# mikrobus-relay-1.net
KiCad netlist of a schematic drawn in EAGLE
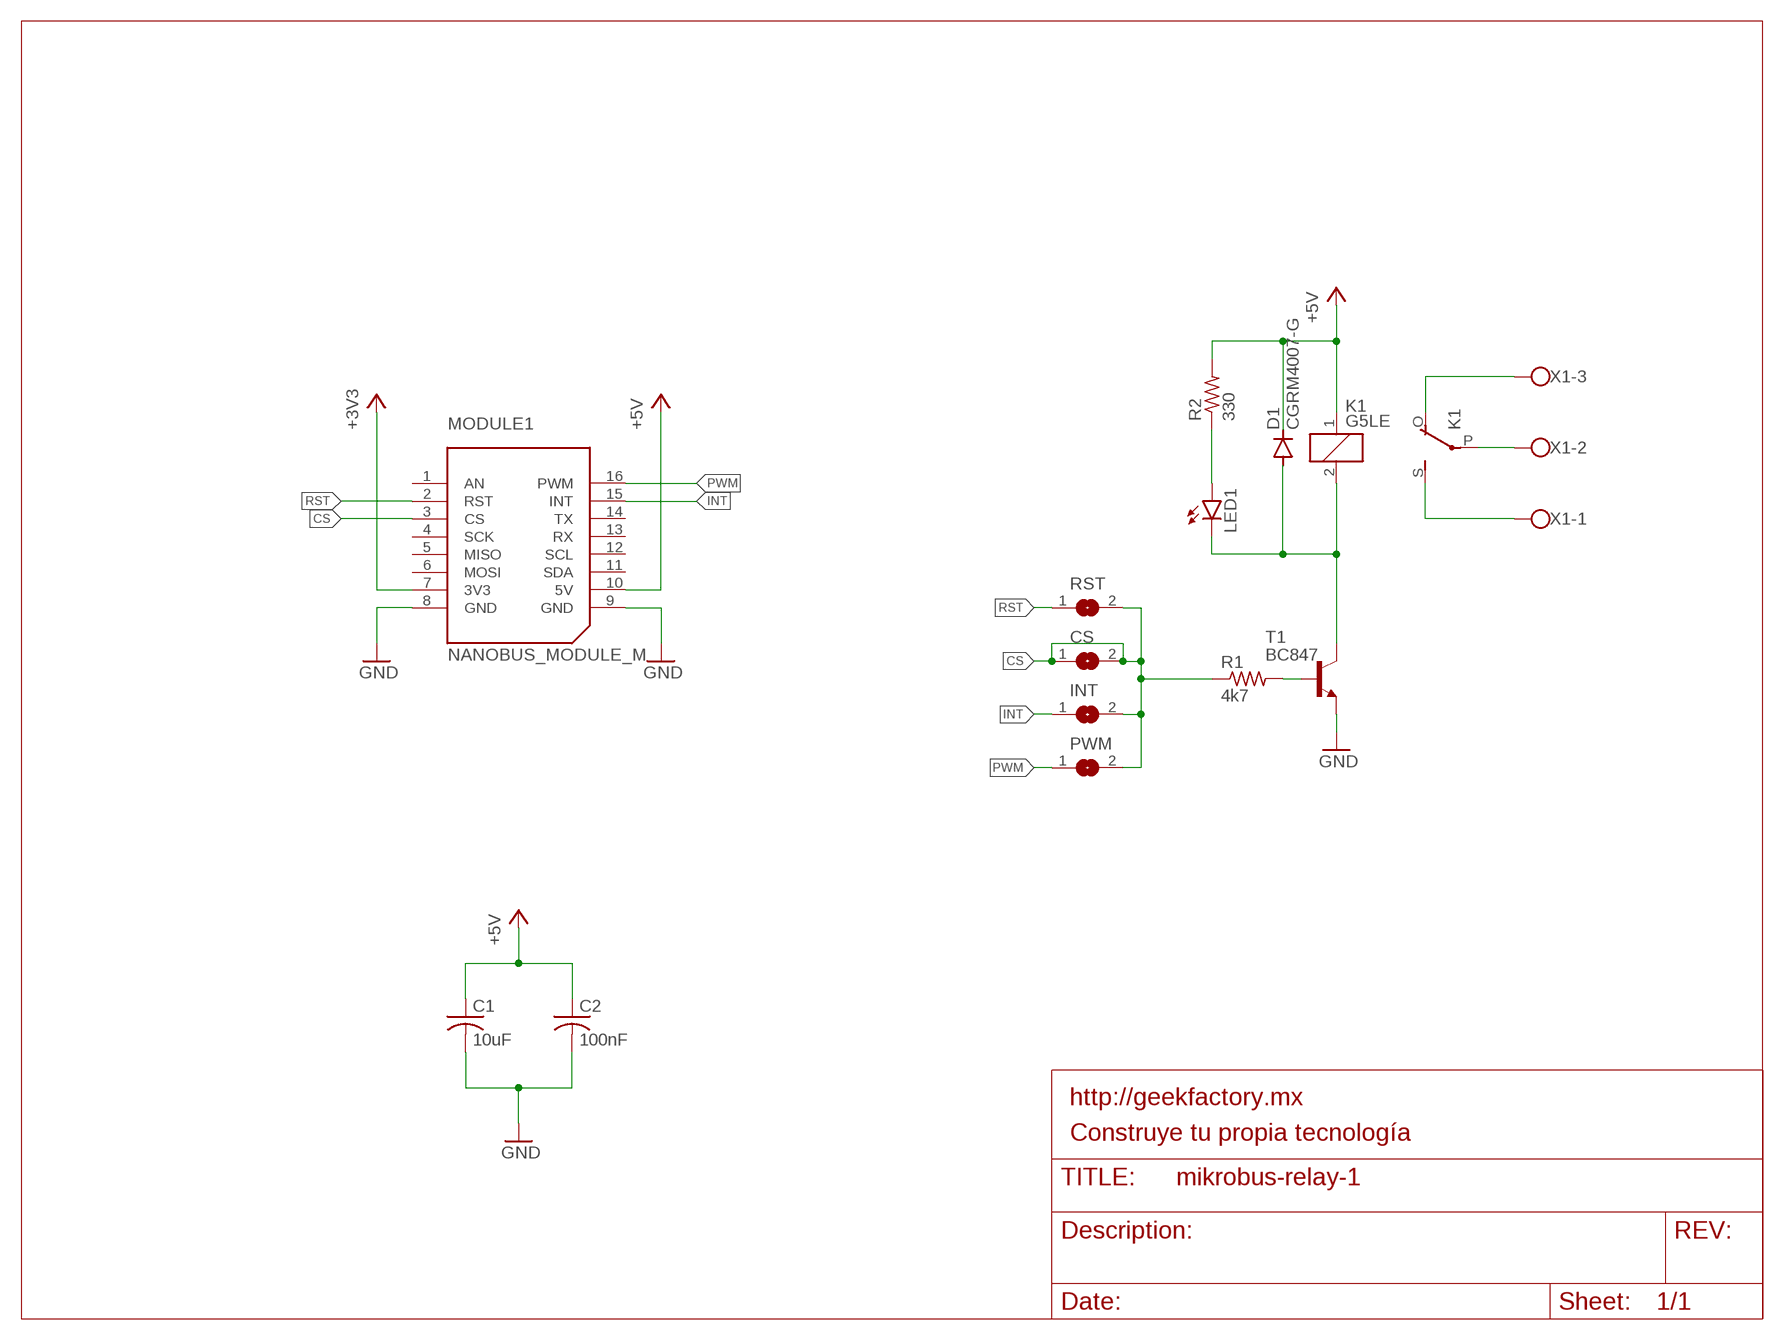
[diagram p0: schematic, sheet 1]

(export (version "E")
  (design (tool "Eeschema 10.0.6"))
  (components
    (comp (ref "C1")
      (value "10uF")
      (footprint "eagle-import:C0805")
      (libsource (lib "eagle-import") (part "C-USC0805"))
    )
    (comp (ref "C2")
      (value "100nF")
      (footprint "eagle-import:C0805")
      (libsource (lib "eagle-import") (part "C-USC0805"))
    )
    (comp (ref "CS") (value "SJ") (footprint "eagle-import:SJ") (libsource (lib "eagle-import") (part "SJ")))
    (comp (ref "D1")
      (value "CGRM4007-G")
      (footprint "eagle-import:SOD-123_MINI-SMA")
      (libsource (lib "eagle-import") (part "CGRM400-G7"))
    )
    (comp (ref "INT") (value "SJ") (footprint "eagle-import:SJ") (libsource (lib "eagle-import") (part "SJ")))
    (comp (ref "K1")
      (value "G5LE")
      (footprint "eagle-import:G5LE")
      (libsource (lib "eagle-import") (part "G5LE"))
    )
    (comp (ref "LED1")
      (value "LEDCHIPLED_0805")
      (footprint "eagle-import:CHIPLED_0805")
      (libsource (lib "eagle-import") (part "LEDCHIPLED_0805"))
    )
    (comp (ref "MODULE1")
      (value "NANOBUS_MODULE_M")
      (footprint "eagle-import:NANOBUS_MODULE_MIDDLE")
      (libsource (lib "eagle-import") (part "NANOBUS_MODULE_M"))
    )
    (comp (ref "PWM") (value "SJ") (footprint "eagle-import:SJ") (libsource (lib "eagle-import") (part "SJ")))
    (comp (ref "R1")
      (value "4k7")
      (footprint "eagle-import:R0805")
      (libsource (lib "eagle-import") (part "R-US_R0805"))
    )
    (comp (ref "R2")
      (value "330")
      (footprint "eagle-import:R0805")
      (libsource (lib "eagle-import") (part "R-US_R0805"))
    )
    (comp (ref "RST") (value "SJ") (footprint "eagle-import:SJ") (libsource (lib "eagle-import") (part "SJ")))
    (comp (ref "T1")
      (value "BC847")
      (footprint "eagle-import:SOT23")
      (libsource (lib "eagle-import") (part "BC847"))
    )
    (comp (ref "X1")
      (value "SCREW-TERMINAL-3-5-0")
      (footprint "eagle-import:SCREW-TERMINAL-5.0MM-3")
      (libsource (lib "eagle-import") (part "SCREW-TERMINAL-3-5-0"))
    )
  )
  (nets
    (net (code "1") (name "+3V3") (class "Default")
      (node (ref "MODULE1") (pin "7") (pinfunction "3V3_7") (pintype "power_in"))
    )
    (net (code "2") (name "+5V") (class "Default")
      (node (ref "C1") (pin "1") (pinfunction "1_1") (pintype "passive"))
      (node (ref "C2") (pin "1") (pinfunction "1_1") (pintype "passive"))
      (node (ref "D1") (pin "C") (pinfunction "C_C") (pintype "passive"))
      (node (ref "K1") (pin "1") (pinfunction "1_1") (pintype "passive"))
      (node (ref "MODULE1") (pin "10") (pinfunction "5V_10") (pintype "power_in"))
      (node (ref "R2") (pin "2") (pinfunction "2_2") (pintype "passive"))
    )
    (net (code "3") (name "CS") (class "Default")
      (node (ref "CS") (pin "1") (pinfunction "1_1") (pintype "passive"))
      (node (ref "CS") (pin "2") (pinfunction "2_2") (pintype "passive"))
      (node (ref "INT") (pin "2") (pinfunction "2_2") (pintype "passive"))
      (node (ref "MODULE1") (pin "3") (pinfunction "CS_3") (pintype "passive"))
      (node (ref "PWM") (pin "2") (pinfunction "2_2") (pintype "passive"))
      (node (ref "R1") (pin "1") (pinfunction "1_1") (pintype "passive"))
      (node (ref "RST") (pin "2") (pinfunction "2_2") (pintype "passive"))
    )
    (net (code "4") (name "GND") (class "Default")
      (node (ref "C1") (pin "2") (pinfunction "2_2") (pintype "passive"))
      (node (ref "C2") (pin "2") (pinfunction "2_2") (pintype "passive"))
      (node (ref "MODULE1") (pin "8") (pinfunction "GND_8") (pintype "power_in"))
      (node (ref "MODULE1") (pin "9") (pinfunction "GND_9") (pintype "power_in"))
      (node (ref "T1") (pin "2") (pinfunction "E_2") (pintype "passive"))
    )
    (net (code "5") (name "INT") (class "Default")
      (node (ref "INT") (pin "1") (pinfunction "1_1") (pintype "passive"))
      (node (ref "MODULE1") (pin "15") (pinfunction "INT_15") (pintype "passive"))
    )
    (net (code "6") (name "Net-(LED1-PadA)") (class "Default")
      (node (ref "LED1") (pin "A") (pinfunction "A_A") (pintype "passive"))
      (node (ref "R2") (pin "1") (pinfunction "1_1") (pintype "passive"))
    )
    (net (code "7") (name "Net-(T1-B)") (class "Default")
      (node (ref "R1") (pin "2") (pinfunction "2_2") (pintype "passive"))
      (node (ref "T1") (pin "1") (pinfunction "B_1") (pintype "passive"))
    )
    (net (code "8") (name "Net-(T1-C)") (class "Default")
      (node (ref "D1") (pin "A") (pinfunction "A_A") (pintype "passive"))
      (node (ref "K1") (pin "2") (pinfunction "2_2") (pintype "passive"))
      (node (ref "LED1") (pin "C") (pinfunction "C_C") (pintype "passive"))
      (node (ref "T1") (pin "3") (pinfunction "C_3") (pintype "passive"))
    )
    (net (code "9") (name "Net-(X1A-PIN)") (class "Default")
      (node (ref "K1") (pin "S") (pinfunction "S_S") (pintype "passive"))
      (node (ref "X1") (pin "1") (pinfunction "PIN_1") (pintype "passive"))
    )
    (net (code "10") (name "Net-(X1B-PIN)") (class "Default")
      (node (ref "K1") (pin "P") (pinfunction "P_P") (pintype "passive"))
      (node (ref "X1") (pin "2") (pinfunction "PIN_2") (pintype "passive"))
    )
    (net (code "11") (name "Net-(X1C-PIN)") (class "Default")
      (node (ref "K1") (pin "O") (pinfunction "O_O") (pintype "passive"))
      (node (ref "X1") (pin "3") (pinfunction "PIN_3") (pintype "passive"))
    )
    (net (code "12") (name "PWM") (class "Default")
      (node (ref "MODULE1") (pin "16") (pinfunction "PWM_16") (pintype "passive"))
      (node (ref "PWM") (pin "1") (pinfunction "1_1") (pintype "passive"))
    )
    (net (code "13") (name "RST") (class "Default")
      (node (ref "MODULE1") (pin "2") (pinfunction "RST_2") (pintype "passive"))
      (node (ref "RST") (pin "1") (pinfunction "1_1") (pintype "passive"))
    )
    (net (code "14") (name "unconnected-(MODULE1-AN-Pad1)") (class "Default")
      (node (ref "MODULE1") (pin "1") (pinfunction "AN_1") (pintype "passive"))
    )
    (net (code "15") (name "unconnected-(MODULE1-MISO-Pad5)") (class "Default")
      (node (ref "MODULE1") (pin "5") (pinfunction "MISO_5") (pintype "passive"))
    )
    (net (code "16") (name "unconnected-(MODULE1-MOSI-Pad6)") (class "Default")
      (node (ref "MODULE1") (pin "6") (pinfunction "MOSI_6") (pintype "passive"))
    )
    (net (code "17") (name "unconnected-(MODULE1-RX-Pad13)") (class "Default")
      (node (ref "MODULE1") (pin "13") (pinfunction "RX_13") (pintype "passive"))
    )
    (net (code "18") (name "unconnected-(MODULE1-SCK-Pad4)") (class "Default")
      (node (ref "MODULE1") (pin "4") (pinfunction "SCK_4") (pintype "passive"))
    )
    (net (code "19") (name "unconnected-(MODULE1-SCL-Pad12)") (class "Default")
      (node (ref "MODULE1") (pin "12") (pinfunction "SCL_12") (pintype "passive"))
    )
    (net (code "20") (name "unconnected-(MODULE1-SDA-Pad11)") (class "Default")
      (node (ref "MODULE1") (pin "11") (pinfunction "SDA_11") (pintype "passive"))
    )
    (net (code "21") (name "unconnected-(MODULE1-TX-Pad14)") (class "Default")
      (node (ref "MODULE1") (pin "14") (pinfunction "TX_14") (pintype "passive"))
    )
  )
)
